# RCS_Cntrl_Board.net
KiCad netlist of a schematic drawn in EAGLE
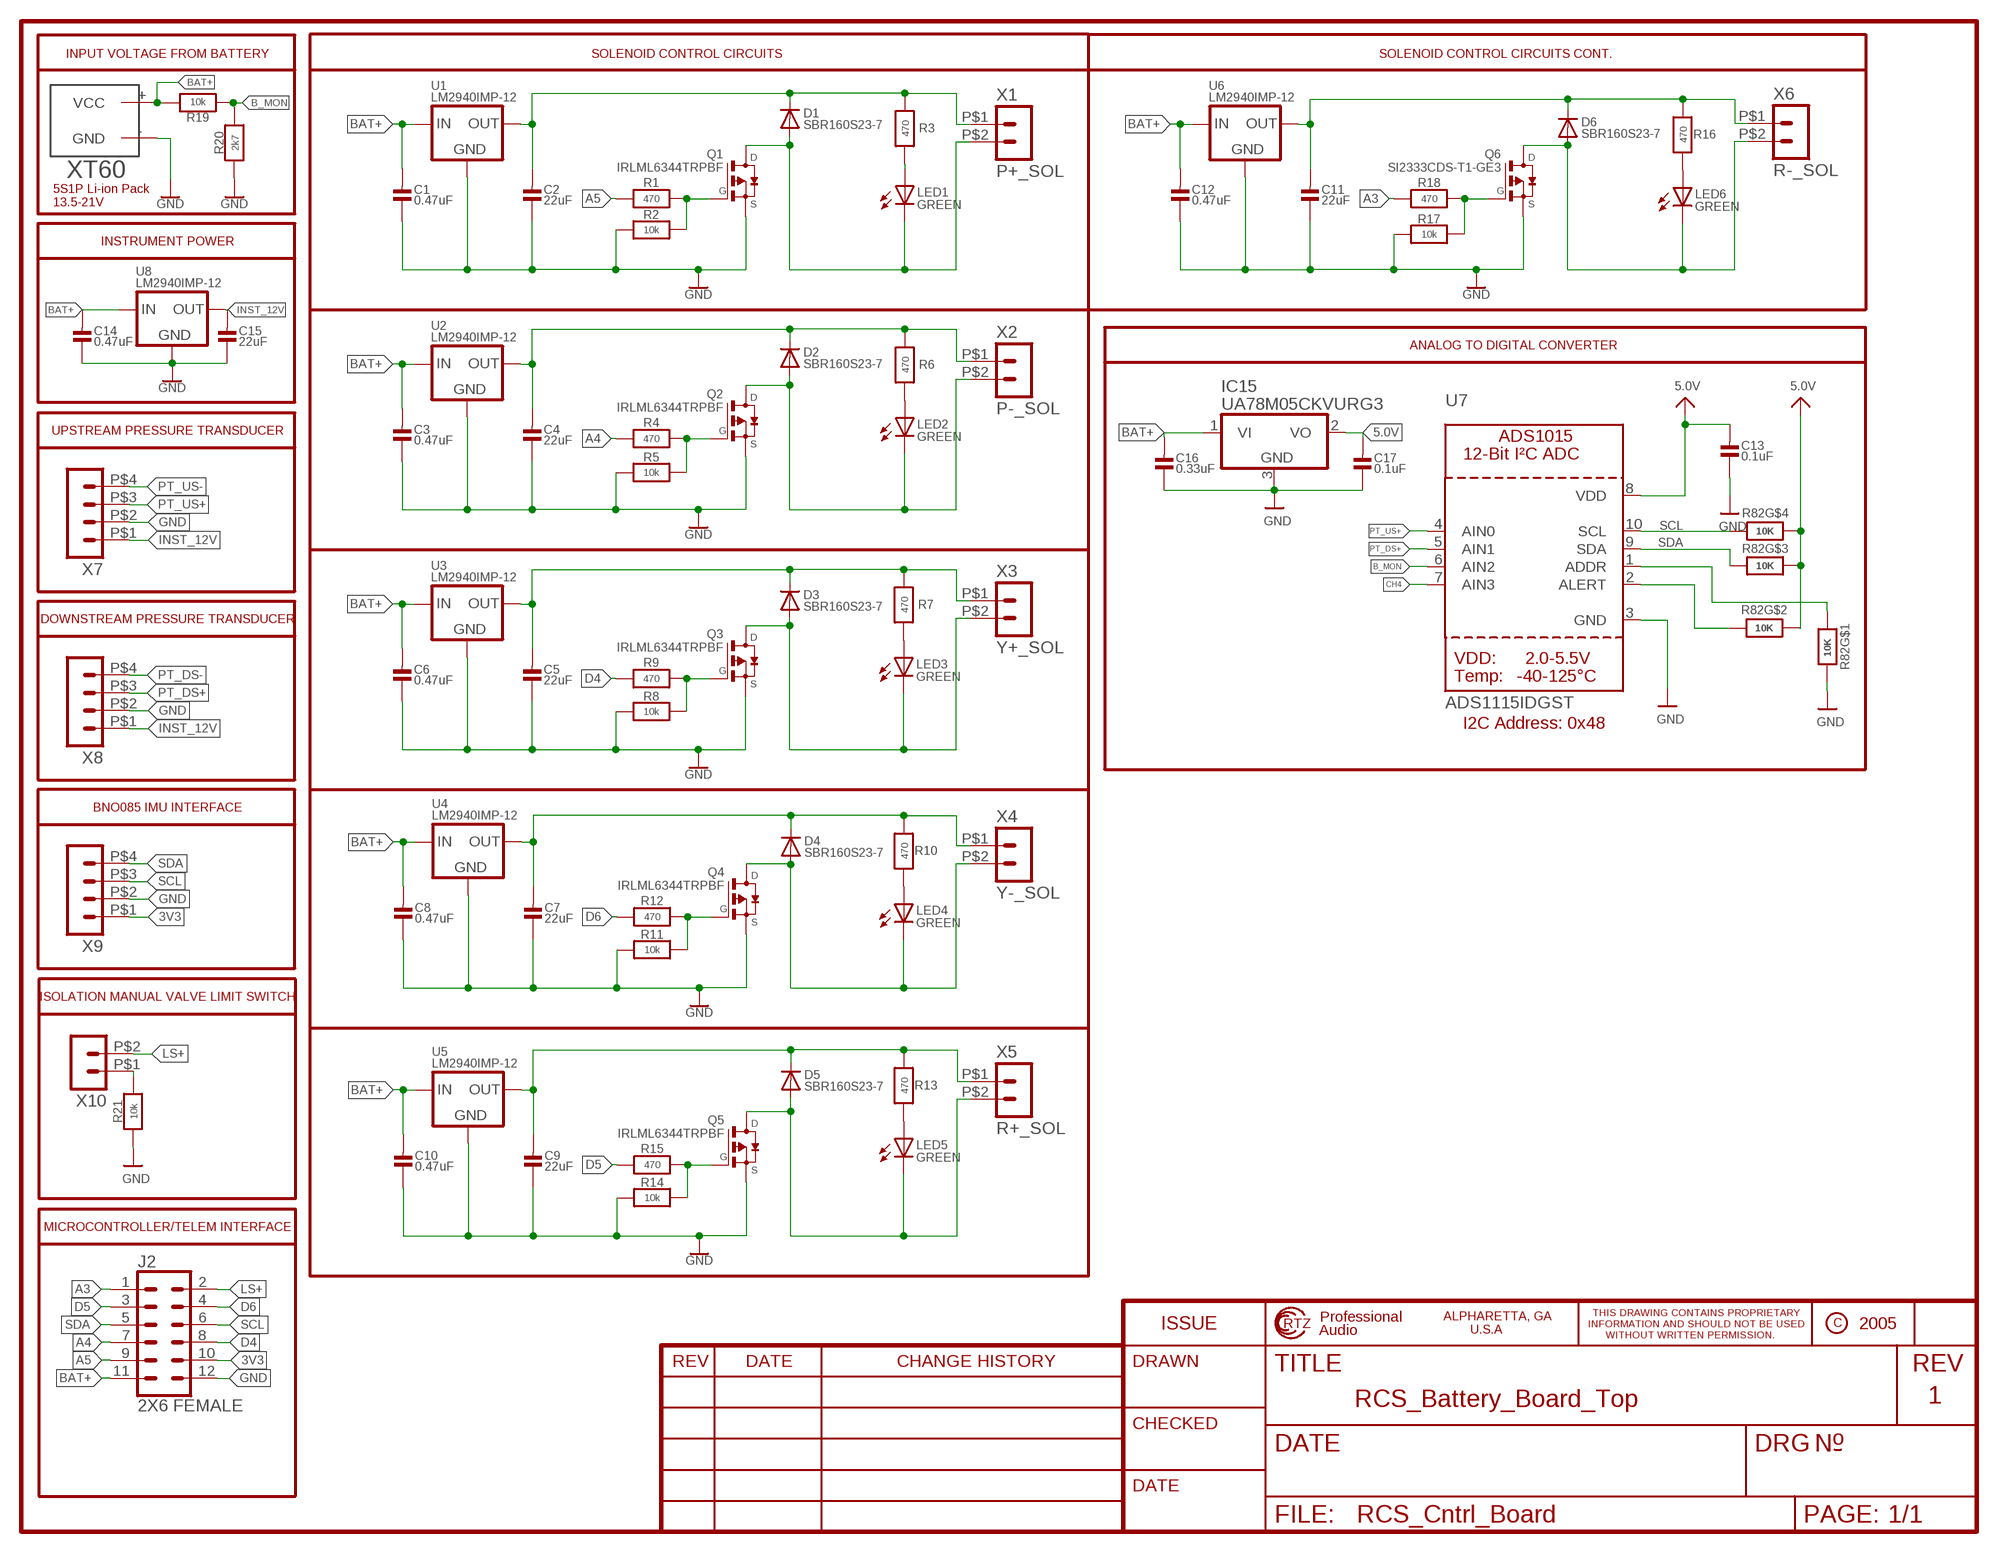
[diagram p0: schematic, sheet 1]

(export (version "E")
  (design (tool "Eeschema 10.0.6"))
  (components
    (comp (ref "C1")
      (value "0.47uF")
      (footprint "eagle-import:0603")
      (libsource (lib "eagle-import") (part "CAP_CERAMIC0603"))
    )
    (comp (ref "C2")
      (value "22uF")
      (footprint "eagle-import:0603")
      (libsource (lib "eagle-import") (part "CAP_CERAMIC0603"))
    )
    (comp (ref "C3")
      (value "0.47uF")
      (footprint "eagle-import:0603")
      (libsource (lib "eagle-import") (part "CAP_CERAMIC0603"))
    )
    (comp (ref "C4")
      (value "22uF")
      (footprint "eagle-import:0603")
      (libsource (lib "eagle-import") (part "CAP_CERAMIC0603"))
    )
    (comp (ref "C5")
      (value "22uF")
      (footprint "eagle-import:0603")
      (libsource (lib "eagle-import") (part "CAP_CERAMIC0603"))
    )
    (comp (ref "C6")
      (value "0.47uF")
      (footprint "eagle-import:0603")
      (libsource (lib "eagle-import") (part "CAP_CERAMIC0603"))
    )
    (comp (ref "C7")
      (value "22uF")
      (footprint "eagle-import:0603")
      (libsource (lib "eagle-import") (part "CAP_CERAMIC0603"))
    )
    (comp (ref "C8")
      (value "0.47uF")
      (footprint "eagle-import:0603")
      (libsource (lib "eagle-import") (part "CAP_CERAMIC0603"))
    )
    (comp (ref "C9")
      (value "22uF")
      (footprint "eagle-import:0603")
      (libsource (lib "eagle-import") (part "CAP_CERAMIC0603"))
    )
    (comp (ref "C10")
      (value "0.47uF")
      (footprint "eagle-import:0603")
      (libsource (lib "eagle-import") (part "CAP_CERAMIC0603"))
    )
    (comp (ref "C11")
      (value "22uF")
      (footprint "eagle-import:0603")
      (libsource (lib "eagle-import") (part "CAP_CERAMIC0603"))
    )
    (comp (ref "C12")
      (value "0.47uF")
      (footprint "eagle-import:0603")
      (libsource (lib "eagle-import") (part "CAP_CERAMIC0603"))
    )
    (comp (ref "C13")
      (value "0.1uF")
      (footprint "eagle-import:0603")
      (libsource (lib "eagle-import") (part "CAP_CERAMIC0603"))
    )
    (comp (ref "C14")
      (value "0.47uF")
      (footprint "eagle-import:0603")
      (libsource (lib "eagle-import") (part "CAP_CERAMIC0603"))
    )
    (comp (ref "C15")
      (value "22uF")
      (footprint "eagle-import:0603")
      (libsource (lib "eagle-import") (part "CAP_CERAMIC0603"))
    )
    (comp (ref "C16")
      (value "0.33uF")
      (footprint "eagle-import:0603")
      (libsource (lib "eagle-import") (part "CAP_CERAMIC0603"))
    )
    (comp (ref "C17")
      (value "0.1uF")
      (footprint "eagle-import:0603")
      (libsource (lib "eagle-import") (part "CAP_CERAMIC0603"))
    )
    (comp (ref "D1")
      (value "SBR160S23-7")
      (footprint "eagle-import:SOT23-R")
      (libsource (lib "eagle-import") (part "DIODESOT23_REFLOW"))
    )
    (comp (ref "D2")
      (value "SBR160S23-7")
      (footprint "eagle-import:SOT23-R")
      (libsource (lib "eagle-import") (part "DIODESOT23_REFLOW"))
    )
    (comp (ref "D3")
      (value "SBR160S23-7")
      (footprint "eagle-import:SOT23-R")
      (libsource (lib "eagle-import") (part "DIODESOT23_REFLOW"))
    )
    (comp (ref "D4")
      (value "SBR160S23-7")
      (footprint "eagle-import:SOT23-R")
      (libsource (lib "eagle-import") (part "DIODESOT23_REFLOW"))
    )
    (comp (ref "D5")
      (value "SBR160S23-7")
      (footprint "eagle-import:SOT23-R")
      (libsource (lib "eagle-import") (part "DIODESOT23_REFLOW"))
    )
    (comp (ref "D6")
      (value "SBR160S23-7")
      (footprint "eagle-import:SOT23-R")
      (libsource (lib "eagle-import") (part "DIODESOT23_REFLOW"))
    )
    (comp (ref "IC15")
      (value "UA78M05CKVURG3")
      (footprint "eagle-import:TO252")
      (libsource (lib "eagle-import") (part "78DT06"))
    )
    (comp (ref "J2")
      (value "2X6 FEMALE")
      (footprint "eagle-import:2X6")
      (libsource (lib "eagle-import") (part "CONN_06X2PTH_FEMALE"))
    )
    (comp (ref "LED1")
      (value "GREEN")
      (footprint "eagle-import:CHIPLED_0603")
      (libsource (lib "eagle-import") (part "LEDCHIPLED_0603"))
    )
    (comp (ref "LED2")
      (value "GREEN")
      (footprint "eagle-import:CHIPLED_0603")
      (libsource (lib "eagle-import") (part "LEDCHIPLED_0603"))
    )
    (comp (ref "LED3")
      (value "GREEN")
      (footprint "eagle-import:CHIPLED_0603")
      (libsource (lib "eagle-import") (part "LEDCHIPLED_0603"))
    )
    (comp (ref "LED4")
      (value "GREEN")
      (footprint "eagle-import:CHIPLED_0603")
      (libsource (lib "eagle-import") (part "LEDCHIPLED_0603"))
    )
    (comp (ref "LED5")
      (value "GREEN")
      (footprint "eagle-import:CHIPLED_0603")
      (libsource (lib "eagle-import") (part "LEDCHIPLED_0603"))
    )
    (comp (ref "LED6")
      (value "GREEN")
      (footprint "eagle-import:CHIPLED_0603")
      (libsource (lib "eagle-import") (part "LEDCHIPLED_0603"))
    )
    (comp (ref "Q1")
      (value "IRLML6344TRPBF")
      (footprint "eagle-import:TRANSISTOR-FET_SOT23")
      (libsource (lib "eagle-import") (part "TRANSISTOR-FET_DMP2004K"))
    )
    (comp (ref "Q2")
      (value "IRLML6344TRPBF")
      (footprint "eagle-import:TRANSISTOR-FET_SOT23")
      (libsource (lib "eagle-import") (part "TRANSISTOR-FET_DMP2004K"))
    )
    (comp (ref "Q3")
      (value "IRLML6344TRPBF")
      (footprint "eagle-import:TRANSISTOR-FET_SOT23")
      (libsource (lib "eagle-import") (part "TRANSISTOR-FET_DMP2004K"))
    )
    (comp (ref "Q4")
      (value "IRLML6344TRPBF")
      (footprint "eagle-import:TRANSISTOR-FET_SOT23")
      (libsource (lib "eagle-import") (part "TRANSISTOR-FET_DMP2004K"))
    )
    (comp (ref "Q5")
      (value "IRLML6344TRPBF")
      (footprint "eagle-import:TRANSISTOR-FET_SOT23")
      (libsource (lib "eagle-import") (part "TRANSISTOR-FET_DMP2004K"))
    )
    (comp (ref "Q6")
      (value "SI2333CDS-T1-GE3")
      (footprint "eagle-import:TRANSISTOR-FET_SOT23")
      (libsource (lib "eagle-import") (part "TRANSISTOR-FET_DMP2004K"))
    )
    (comp (ref "R1")
      (value "470")
      (footprint "eagle-import:0603-NO")
      (libsource (lib "eagle-import") (part "RESISTOR_0603_NOOUT"))
    )
    (comp (ref "R2")
      (value "10k")
      (footprint "eagle-import:0603-NO")
      (libsource (lib "eagle-import") (part "RESISTOR_0603_NOOUT"))
    )
    (comp (ref "R3")
      (value "470")
      (footprint "eagle-import:0603-NO")
      (libsource (lib "eagle-import") (part "RESISTOR_0603_NOOUT"))
    )
    (comp (ref "R4")
      (value "470")
      (footprint "eagle-import:0603-NO")
      (libsource (lib "eagle-import") (part "RESISTOR_0603_NOOUT"))
    )
    (comp (ref "R5")
      (value "10k")
      (footprint "eagle-import:0603-NO")
      (libsource (lib "eagle-import") (part "RESISTOR_0603_NOOUT"))
    )
    (comp (ref "R6")
      (value "470")
      (footprint "eagle-import:0603-NO")
      (libsource (lib "eagle-import") (part "RESISTOR_0603_NOOUT"))
    )
    (comp (ref "R7")
      (value "470")
      (footprint "eagle-import:0603-NO")
      (libsource (lib "eagle-import") (part "RESISTOR_0603_NOOUT"))
    )
    (comp (ref "R8")
      (value "10k")
      (footprint "eagle-import:0603-NO")
      (libsource (lib "eagle-import") (part "RESISTOR_0603_NOOUT"))
    )
    (comp (ref "R9")
      (value "470")
      (footprint "eagle-import:0603-NO")
      (libsource (lib "eagle-import") (part "RESISTOR_0603_NOOUT"))
    )
    (comp (ref "R10")
      (value "470")
      (footprint "eagle-import:0603-NO")
      (libsource (lib "eagle-import") (part "RESISTOR_0603_NOOUT"))
    )
    (comp (ref "R11")
      (value "10k")
      (footprint "eagle-import:0603-NO")
      (libsource (lib "eagle-import") (part "RESISTOR_0603_NOOUT"))
    )
    (comp (ref "R12")
      (value "470")
      (footprint "eagle-import:0603-NO")
      (libsource (lib "eagle-import") (part "RESISTOR_0603_NOOUT"))
    )
    (comp (ref "R13")
      (value "470")
      (footprint "eagle-import:0603-NO")
      (libsource (lib "eagle-import") (part "RESISTOR_0603_NOOUT"))
    )
    (comp (ref "R14")
      (value "10k")
      (footprint "eagle-import:0603-NO")
      (libsource (lib "eagle-import") (part "RESISTOR_0603_NOOUT"))
    )
    (comp (ref "R15")
      (value "470")
      (footprint "eagle-import:0603-NO")
      (libsource (lib "eagle-import") (part "RESISTOR_0603_NOOUT"))
    )
    (comp (ref "R16")
      (value "470")
      (footprint "eagle-import:0603-NO")
      (libsource (lib "eagle-import") (part "RESISTOR_0603_NOOUT"))
    )
    (comp (ref "R17")
      (value "10k")
      (footprint "eagle-import:0603-NO")
      (libsource (lib "eagle-import") (part "RESISTOR_0603_NOOUT"))
    )
    (comp (ref "R18")
      (value "470")
      (footprint "eagle-import:0603-NO")
      (libsource (lib "eagle-import") (part "RESISTOR_0603_NOOUT"))
    )
    (comp (ref "R19")
      (value "10k")
      (footprint "eagle-import:0603-NO")
      (libsource (lib "eagle-import") (part "RESISTOR_0603_NOOUT"))
    )
    (comp (ref "R20")
      (value "2k7")
      (footprint "eagle-import:0603-NO")
      (libsource (lib "eagle-import") (part "RESISTOR_0603_NOOUT"))
    )
    (comp (ref "R21")
      (value "10k")
      (footprint "eagle-import:0603-NO")
      (libsource (lib "eagle-import") (part "RESISTOR_0603_NOOUT"))
    )
    (comp (ref "R82")
      (value "10K")
      (footprint "eagle-import:RESPACK_4X0603")
      (libsource (lib "eagle-import") (part "RESISTOR_4PACK"))
    )
    (comp (ref "U$4")
      (value "XT60")
      (footprint "eagle-import:XT60")
      (libsource (lib "eagle-import") (part "XT60"))
    )
    (comp (ref "U1")
      (value "LM2940IMP-12")
      (footprint "eagle-import:SOT223-R")
      (libsource (lib "eagle-import") (part "LM2940IMP-12/NOPB"))
    )
    (comp (ref "U2")
      (value "LM2940IMP-12")
      (footprint "eagle-import:SOT223-R")
      (libsource (lib "eagle-import") (part "LM2940IMP-12/NOPB"))
    )
    (comp (ref "U3")
      (value "LM2940IMP-12")
      (footprint "eagle-import:SOT223-R")
      (libsource (lib "eagle-import") (part "LM2940IMP-12/NOPB"))
    )
    (comp (ref "U4")
      (value "LM2940IMP-12")
      (footprint "eagle-import:SOT223-R")
      (libsource (lib "eagle-import") (part "LM2940IMP-12/NOPB"))
    )
    (comp (ref "U5")
      (value "LM2940IMP-12")
      (footprint "eagle-import:SOT223-R")
      (libsource (lib "eagle-import") (part "LM2940IMP-12/NOPB"))
    )
    (comp (ref "U6")
      (value "LM2940IMP-12")
      (footprint "eagle-import:SOT223-R")
      (libsource (lib "eagle-import") (part "LM2940IMP-12/NOPB"))
    )
    (comp (ref "U7")
      (value "ADS1115IDGST")
      (footprint "eagle-import:MSOP10")
      (libsource (lib "eagle-import") (part "ADC_ADS1015"))
    )
    (comp (ref "U8")
      (value "LM2940IMP-12")
      (footprint "eagle-import:SOT223-R")
      (libsource (lib "eagle-import") (part "LM2940IMP-12/NOPB"))
    )
    (comp (ref "X1")
      (value "P+_SOL")
      (footprint "eagle-import:44914-0201")
      (libsource (lib "eagle-import") (part "HEADER_POS2_?44914-0201"))
    )
    (comp (ref "X2")
      (value "P-_SOL")
      (footprint "eagle-import:44914-0201")
      (libsource (lib "eagle-import") (part "HEADER_POS2_?44914-0201"))
    )
    (comp (ref "X3")
      (value "Y+_SOL")
      (footprint "eagle-import:44914-0201")
      (libsource (lib "eagle-import") (part "HEADER_POS2_?44914-0201"))
    )
    (comp (ref "X4")
      (value "Y-_SOL")
      (footprint "eagle-import:44914-0201")
      (libsource (lib "eagle-import") (part "HEADER_POS2_?44914-0201"))
    )
    (comp (ref "X5")
      (value "R+_SOL")
      (footprint "eagle-import:44914-0201")
      (libsource (lib "eagle-import") (part "HEADER_POS2_?44914-0201"))
    )
    (comp (ref "X6")
      (value "R-_SOL")
      (footprint "eagle-import:44914-0201")
      (libsource (lib "eagle-import") (part "HEADER_POS2_?44914-0201"))
    )
    (comp (ref "X7")
      (value "HEADER_POS4_43650-0415")
      (footprint "eagle-import:43650-0415")
      (libsource (lib "eagle-import") (part "HEADER_POS4_?43650-0415"))
    )
    (comp (ref "X8")
      (value "HEADER_POS4_43650-0415")
      (footprint "eagle-import:43650-0415")
      (libsource (lib "eagle-import") (part "HEADER_POS4_?43650-0415"))
    )
    (comp (ref "X9")
      (value "HEADER_POS4_43650-0415")
      (footprint "eagle-import:43650-0415")
      (libsource (lib "eagle-import") (part "HEADER_POS4_?43650-0415"))
    )
    (comp (ref "X10")
      (value "HEADER_POS2_43650-0215")
      (footprint "eagle-import:43650-0215")
      (libsource (lib "eagle-import") (part "HEADER_POS2_?43650-0215"))
    )
  )
  (nets
    (net (code "1") (name "3V3") (class "Default")
      (node (ref "J2") (pin "10") (pinfunction "10_10") (pintype "passive"))
      (node (ref "X9") (pin "P$1") (pinfunction "1_P$1") (pintype "passive"))
    )
    (net (code "2") (name "5.0V") (class "Default")
      (node (ref "C13") (pin "2") (pinfunction "P$2_2") (pintype "passive"))
      (node (ref "C17") (pin "2") (pinfunction "P$2_2") (pintype "passive"))
      (node (ref "IC15") (pin "2") (pinfunction "VO_2") (pintype "passive"))
      (node (ref "R82") (pin "5") (pinfunction "2_5") (pintype "passive"))
      (node (ref "R82") (pin "6") (pinfunction "2_6") (pintype "passive"))
      (node (ref "R82") (pin "7") (pinfunction "2_7") (pintype "passive"))
      (node (ref "U7") (pin "8") (pinfunction "VDD_8") (pintype "bidirectional"))
    )
    (net (code "3") (name "A3") (class "Default")
      (node (ref "J2") (pin "1") (pinfunction "1_1") (pintype "passive"))
      (node (ref "R18") (pin "1") (pinfunction "1_1") (pintype "passive"))
    )
    (net (code "4") (name "A4") (class "Default")
      (node (ref "J2") (pin "7") (pinfunction "7_7") (pintype "passive"))
      (node (ref "R4") (pin "1") (pinfunction "1_1") (pintype "passive"))
    )
    (net (code "5") (name "A5") (class "Default")
      (node (ref "J2") (pin "9") (pinfunction "9_9") (pintype "passive"))
      (node (ref "R1") (pin "1") (pinfunction "1_1") (pintype "passive"))
    )
    (net (code "6") (name "BAT+") (class "Default")
      (node (ref "C1") (pin "2") (pinfunction "P$2_2") (pintype "passive"))
      (node (ref "C10") (pin "2") (pinfunction "P$2_2") (pintype "passive"))
      (node (ref "C12") (pin "2") (pinfunction "P$2_2") (pintype "passive"))
      (node (ref "C14") (pin "2") (pinfunction "P$2_2") (pintype "passive"))
      (node (ref "C16") (pin "2") (pinfunction "P$2_2") (pintype "passive"))
      (node (ref "C3") (pin "2") (pinfunction "P$2_2") (pintype "passive"))
      (node (ref "C6") (pin "2") (pinfunction "P$2_2") (pintype "passive"))
      (node (ref "C8") (pin "2") (pinfunction "P$2_2") (pintype "passive"))
      (node (ref "IC15") (pin "1") (pinfunction "VI_1") (pintype "input"))
      (node (ref "J2") (pin "11") (pinfunction "11_11") (pintype "passive"))
      (node (ref "R19") (pin "2") (pinfunction "2_2") (pintype "passive"))
      (node (ref "U$4") (pin "+") (pinfunction "VCC_+") (pintype "bidirectional"))
      (node (ref "U1") (pin "1") (pinfunction "IN_1") (pintype "input"))
      (node (ref "U2") (pin "1") (pinfunction "IN_1") (pintype "input"))
      (node (ref "U3") (pin "1") (pinfunction "IN_1") (pintype "input"))
      (node (ref "U4") (pin "1") (pinfunction "IN_1") (pintype "input"))
      (node (ref "U5") (pin "1") (pinfunction "IN_1") (pintype "input"))
      (node (ref "U6") (pin "1") (pinfunction "IN_1") (pintype "input"))
      (node (ref "U8") (pin "1") (pinfunction "IN_1") (pintype "input"))
    )
    (net (code "7") (name "B_MON") (class "Default")
      (node (ref "R19") (pin "1") (pinfunction "1_1") (pintype "passive"))
      (node (ref "R20") (pin "2") (pinfunction "2_2") (pintype "passive"))
      (node (ref "U7") (pin "6") (pinfunction "AIN2_6") (pintype "bidirectional"))
    )
    (net (code "8") (name "CH4") (class "Default")
      (node (ref "U7") (pin "7") (pinfunction "AIN3_7") (pintype "bidirectional"))
    )
    (net (code "9") (name "D4") (class "Default")
      (node (ref "J2") (pin "8") (pinfunction "8_8") (pintype "passive"))
      (node (ref "R9") (pin "1") (pinfunction "1_1") (pintype "passive"))
    )
    (net (code "10") (name "D5") (class "Default")
      (node (ref "J2") (pin "3") (pinfunction "3_3") (pintype "passive"))
      (node (ref "R15") (pin "1") (pinfunction "1_1") (pintype "passive"))
    )
    (net (code "11") (name "D6") (class "Default")
      (node (ref "J2") (pin "4") (pinfunction "4_4") (pintype "passive"))
      (node (ref "R12") (pin "1") (pinfunction "1_1") (pintype "passive"))
    )
    (net (code "12") (name "GND") (class "Default")
      (node (ref "C1") (pin "1") (pinfunction "P$1_1") (pintype "passive"))
      (node (ref "C10") (pin "1") (pinfunction "P$1_1") (pintype "passive"))
      (node (ref "C11") (pin "1") (pinfunction "P$1_1") (pintype "passive"))
      (node (ref "C12") (pin "1") (pinfunction "P$1_1") (pintype "passive"))
      (node (ref "C13") (pin "1") (pinfunction "P$1_1") (pintype "passive"))
      (node (ref "C14") (pin "1") (pinfunction "P$1_1") (pintype "passive"))
      (node (ref "C15") (pin "1") (pinfunction "P$1_1") (pintype "passive"))
      (node (ref "C16") (pin "1") (pinfunction "P$1_1") (pintype "passive"))
      (node (ref "C17") (pin "1") (pinfunction "P$1_1") (pintype "passive"))
      (node (ref "C2") (pin "1") (pinfunction "P$1_1") (pintype "passive"))
      (node (ref "C3") (pin "1") (pinfunction "P$1_1") (pintype "passive"))
      (node (ref "C4") (pin "1") (pinfunction "P$1_1") (pintype "passive"))
      (node (ref "C5") (pin "1") (pinfunction "P$1_1") (pintype "passive"))
      (node (ref "C6") (pin "1") (pinfunction "P$1_1") (pintype "passive"))
      (node (ref "C7") (pin "1") (pinfunction "P$1_1") (pintype "passive"))
      (node (ref "C8") (pin "1") (pinfunction "P$1_1") (pintype "passive"))
      (node (ref "C9") (pin "1") (pinfunction "P$1_1") (pintype "passive"))
      (node (ref "IC15") (pin "3") (pinfunction "GND_3") (pintype "passive"))
      (node (ref "J2") (pin "12") (pinfunction "12_12") (pintype "passive"))
      (node (ref "Q1") (pin "2") (pinfunction "S_2") (pintype "passive"))
      (node (ref "Q2") (pin "2") (pinfunction "S_2") (pintype "passive"))
      (node (ref "Q3") (pin "2") (pinfunction "S_2") (pintype "passive"))
      (node (ref "Q4") (pin "2") (pinfunction "S_2") (pintype "passive"))
      (node (ref "Q5") (pin "2") (pinfunction "S_2") (pintype "passive"))
      (node (ref "Q6") (pin "2") (pinfunction "S_2") (pintype "passive"))
      (node (ref "R11") (pin "1") (pinfunction "1_1") (pintype "passive"))
      (node (ref "R14") (pin "1") (pinfunction "1_1") (pintype "passive"))
      (node (ref "R17") (pin "1") (pinfunction "1_1") (pintype "passive"))
      (node (ref "R2") (pin "1") (pinfunction "1_1") (pintype "passive"))
      (node (ref "R20") (pin "1") (pinfunction "1_1") (pintype "passive"))
      (node (ref "R21") (pin "1") (pinfunction "1_1") (pintype "passive"))
      (node (ref "R5") (pin "1") (pinfunction "1_1") (pintype "passive"))
      (node (ref "R8") (pin "1") (pinfunction "1_1") (pintype "passive"))
      (node (ref "R82") (pin "8") (pinfunction "2_8") (pintype "passive"))
      (node (ref "U$4") (pin "-") (pinfunction "GND_-") (pintype "bidirectional"))
      (node (ref "U1") (pin "2") (pinfunction "GND_2") (pintype "input"))
      (node (ref "U2") (pin "2") (pinfunction "GND_2") (pintype "input"))
      (node (ref "U3") (pin "2") (pinfunction "GND_2") (pintype "input"))
      (node (ref "U4") (pin "2") (pinfunction "GND_2") (pintype "input"))
      (node (ref "U5") (pin "2") (pinfunction "GND_2") (pintype "input"))
      (node (ref "U6") (pin "2") (pinfunction "GND_2") (pintype "input"))
      (node (ref "U7") (pin "3") (pinfunction "GND_3") (pintype "bidirectional"))
      (node (ref "U8") (pin "2") (pinfunction "GND_2") (pintype "input"))
      (node (ref "X7") (pin "P$2") (pinfunction "2_P$2") (pintype "passive"))
      (node (ref "X8") (pin "P$2") (pinfunction "2_P$2") (pintype "passive"))
      (node (ref "X9") (pin "P$2") (pinfunction "2_P$2") (pintype "passive"))
    )
    (net (code "13") (name "INST_12V") (class "Default")
      (node (ref "C15") (pin "2") (pinfunction "P$2_2") (pintype "passive"))
      (node (ref "U8") (pin "3") (pinfunction "OUT_3") (pintype "passive"))
      (node (ref "X7") (pin "P$1") (pinfunction "1_P$1") (pintype "passive"))
      (node (ref "X8") (pin "P$1") (pinfunction "1_P$1") (pintype "passive"))
    )
    (net (code "14") (name "LS+") (class "Default")
      (node (ref "J2") (pin "2") (pinfunction "2_2") (pintype "passive"))
      (node (ref "X10") (pin "P$2") (pinfunction "2_P$2") (pintype "passive"))
    )
    (net (code "15") (name "Net-(C2-P$2)") (class "Default")
      (node (ref "C2") (pin "2") (pinfunction "P$2_2") (pintype "passive"))
      (node (ref "D1") (pin "3") (pinfunction "C_3") (pintype "passive"))
      (node (ref "R3") (pin "2") (pinfunction "2_2") (pintype "passive"))
      (node (ref "U1") (pin "3") (pinfunction "OUT_3") (pintype "passive"))
      (node (ref "X1") (pin "P$1") (pinfunction "1_P$1") (pintype "passive"))
    )
    (net (code "16") (name "Net-(C4-P$2)") (class "Default")
      (node (ref "C4") (pin "2") (pinfunction "P$2_2") (pintype "passive"))
      (node (ref "D2") (pin "3") (pinfunction "C_3") (pintype "passive"))
      (node (ref "R6") (pin "2") (pinfunction "2_2") (pintype "passive"))
      (node (ref "U2") (pin "3") (pinfunction "OUT_3") (pintype "passive"))
      (node (ref "X2") (pin "P$1") (pinfunction "1_P$1") (pintype "passive"))
    )
    (net (code "17") (name "Net-(C5-P$2)") (class "Default")
      (node (ref "C5") (pin "2") (pinfunction "P$2_2") (pintype "passive"))
      (node (ref "D3") (pin "3") (pinfunction "C_3") (pintype "passive"))
      (node (ref "R7") (pin "2") (pinfunction "2_2") (pintype "passive"))
      (node (ref "U3") (pin "3") (pinfunction "OUT_3") (pintype "passive"))
      (node (ref "X3") (pin "P$1") (pinfunction "1_P$1") (pintype "passive"))
    )
    (net (code "18") (name "Net-(C7-P$2)") (class "Default")
      (node (ref "C7") (pin "2") (pinfunction "P$2_2") (pintype "passive"))
      (node (ref "D4") (pin "3") (pinfunction "C_3") (pintype "passive"))
      (node (ref "R10") (pin "2") (pinfunction "2_2") (pintype "passive"))
      (node (ref "U4") (pin "3") (pinfunction "OUT_3") (pintype "passive"))
      (node (ref "X4") (pin "P$1") (pinfunction "1_P$1") (pintype "passive"))
    )
    (net (code "19") (name "Net-(C9-P$2)") (class "Default")
      (node (ref "C9") (pin "2") (pinfunction "P$2_2") (pintype "passive"))
      (node (ref "D5") (pin "3") (pinfunction "C_3") (pintype "passive"))
      (node (ref "R13") (pin "2") (pinfunction "2_2") (pintype "passive"))
      (node (ref "U5") (pin "3") (pinfunction "OUT_3") (pintype "passive"))
      (node (ref "X5") (pin "P$1") (pinfunction "1_P$1") (pintype "passive"))
    )
    (net (code "20") (name "Net-(C11-P$2)") (class "Default")
      (node (ref "C11") (pin "2") (pinfunction "P$2_2") (pintype "passive"))
      (node (ref "D6") (pin "3") (pinfunction "C_3") (pintype "passive"))
      (node (ref "R16") (pin "2") (pinfunction "2_2") (pintype "passive"))
      (node (ref "U6") (pin "3") (pinfunction "OUT_3") (pintype "passive"))
      (node (ref "X6") (pin "P$1") (pinfunction "1_P$1") (pintype "passive"))
    )
    (net (code "21") (name "Net-(D1-A)") (class "Default")
      (node (ref "D1") (pin "1") (pinfunction "A_1") (pintype "passive"))
      (node (ref "LED1") (pin "C") (pinfunction "C_C") (pintype "passive"))
      (node (ref "Q1") (pin "3") (pinfunction "D_3") (pintype "passive"))
      (node (ref "X1") (pin "P$2") (pinfunction "2_P$2") (pintype "passive"))
    )
    (net (code "22") (name "Net-(D2-A)") (class "Default")
      (node (ref "D2") (pin "1") (pinfunction "A_1") (pintype "passive"))
      (node (ref "LED2") (pin "C") (pinfunction "C_C") (pintype "passive"))
      (node (ref "Q2") (pin "3") (pinfunction "D_3") (pintype "passive"))
      (node (ref "X2") (pin "P$2") (pinfunction "2_P$2") (pintype "passive"))
    )
    (net (code "23") (name "Net-(D3-A)") (class "Default")
      (node (ref "D3") (pin "1") (pinfunction "A_1") (pintype "passive"))
      (node (ref "LED3") (pin "C") (pinfunction "C_C") (pintype "passive"))
      (node (ref "Q3") (pin "3") (pinfunction "D_3") (pintype "passive"))
      (node (ref "X3") (pin "P$2") (pinfunction "2_P$2") (pintype "passive"))
    )
    (net (code "24") (name "Net-(D4-A)") (class "Default")
      (node (ref "D4") (pin "1") (pinfunction "A_1") (pintype "passive"))
      (node (ref "LED4") (pin "C") (pinfunction "C_C") (pintype "passive"))
      (node (ref "Q4") (pin "3") (pinfunction "D_3") (pintype "passive"))
      (node (ref "X4") (pin "P$2") (pinfunction "2_P$2") (pintype "passive"))
    )
    (net (code "25") (name "Net-(D5-A)") (class "Default")
      (node (ref "D5") (pin "1") (pinfunction "A_1") (pintype "passive"))
      (node (ref "LED5") (pin "C") (pinfunction "C_C") (pintype "passive"))
      (node (ref "Q5") (pin "3") (pinfunction "D_3") (pintype "passive"))
      (node (ref "X5") (pin "P$2") (pinfunction "2_P$2") (pintype "passive"))
    )
    (net (code "26") (name "Net-(D6-A)") (class "Default")
      (node (ref "D6") (pin "1") (pinfunction "A_1") (pintype "passive"))
      (node (ref "LED6") (pin "C") (pinfunction "C_C") (pintype "passive"))
      (node (ref "Q6") (pin "3") (pinfunction "D_3") (pintype "passive"))
      (node (ref "X6") (pin "P$2") (pinfunction "2_P$2") (pintype "passive"))
    )
    (net (code "27") (name "Net-(LED1-PadA)") (class "Default")
      (node (ref "LED1") (pin "A") (pinfunction "A_A") (pintype "passive"))
      (node (ref "R3") (pin "1") (pinfunction "1_1") (pintype "passive"))
    )
    (net (code "28") (name "Net-(LED2-PadA)") (class "Default")
      (node (ref "LED2") (pin "A") (pinfunction "A_A") (pintype "passive"))
      (node (ref "R6") (pin "1") (pinfunction "1_1") (pintype "passive"))
    )
    (net (code "29") (name "Net-(LED3-PadA)") (class "Default")
      (node (ref "LED3") (pin "A") (pinfunction "A_A") (pintype "passive"))
      (node (ref "R7") (pin "1") (pinfunction "1_1") (pintype "passive"))
    )
    (net (code "30") (name "Net-(LED4-PadA)") (class "Default")
      (node (ref "LED4") (pin "A") (pinfunction "A_A") (pintype "passive"))
      (node (ref "R10") (pin "1") (pinfunction "1_1") (pintype "passive"))
    )
    (net (code "31") (name "Net-(LED5-PadA)") (class "Default")
      (node (ref "LED5") (pin "A") (pinfunction "A_A") (pintype "passive"))
      (node (ref "R13") (pin "1") (pinfunction "1_1") (pintype "passive"))
    )
    (net (code "32") (name "Net-(LED6-PadA)") (class "Default")
      (node (ref "LED6") (pin "A") (pinfunction "A_A") (pintype "passive"))
      (node (ref "R16") (pin "1") (pinfunction "1_1") (pintype "passive"))
    )
    (net (code "33") (name "Net-(Q1-G)") (class "Default")
      (node (ref "Q1") (pin "1") (pinfunction "G_1") (pintype "passive"))
      (node (ref "R1") (pin "2") (pinfunction "2_2") (pintype "passive"))
      (node (ref "R2") (pin "2") (pinfunction "2_2") (pintype "passive"))
    )
    (net (code "34") (name "Net-(Q2-G)") (class "Default")
      (node (ref "Q2") (pin "1") (pinfunction "G_1") (pintype "passive"))
      (node (ref "R4") (pin "2") (pinfunction "2_2") (pintype "passive"))
      (node (ref "R5") (pin "2") (pinfunction "2_2") (pintype "passive"))
    )
    (net (code "35") (name "Net-(Q3-G)") (class "Default")
      (node (ref "Q3") (pin "1") (pinfunction "G_1") (pintype "passive"))
      (node (ref "R8") (pin "2") (pinfunction "2_2") (pintype "passive"))
      (node (ref "R9") (pin "2") (pinfunction "2_2") (pintype "passive"))
    )
    (net (code "36") (name "Net-(Q4-G)") (class "Default")
      (node (ref "Q4") (pin "1") (pinfunction "G_1") (pintype "passive"))
      (node (ref "R11") (pin "2") (pinfunction "2_2") (pintype "passive"))
      (node (ref "R12") (pin "2") (pinfunction "2_2") (pintype "passive"))
    )
    (net (code "37") (name "Net-(Q5-G)") (class "Default")
      (node (ref "Q5") (pin "1") (pinfunction "G_1") (pintype "passive"))
      (node (ref "R14") (pin "2") (pinfunction "2_2") (pintype "passive"))
      (node (ref "R15") (pin "2") (pinfunction "2_2") (pintype "passive"))
    )
    (net (code "38") (name "Net-(Q6-G)") (class "Default")
      (node (ref "Q6") (pin "1") (pinfunction "G_1") (pintype "passive"))
      (node (ref "R17") (pin "2") (pinfunction "2_2") (pintype "passive"))
      (node (ref "R18") (pin "2") (pinfunction "2_2") (pintype "passive"))
    )
    (net (code "39") (name "Net-(R82B-1)") (class "Default")
      (node (ref "R82") (pin "2") (pinfunction "1_2") (pintype "passive"))
      (node (ref "U7") (pin "2") (pinfunction "ALERT_2") (pintype "bidirectional"))
    )
    (net (code "40") (name "Net-(U7-ADDR)") (class "Default")
      (node (ref "R82") (pin "1") (pinfunction "1_1") (pintype "passive"))
      (node (ref "U7") (pin "1") (pinfunction "ADDR_1") (pintype "bidirectional"))
    )
    (net (code "41") (name "Net-(X10-1)") (class "Default")
      (node (ref "R21") (pin "2") (pinfunction "2_2") (pintype "passive"))
      (node (ref "X10") (pin "P$1") (pinfunction "1_P$1") (pintype "passive"))
    )
    (net (code "42") (name "PT_DS+") (class "Default")
      (node (ref "U7") (pin "5") (pinfunction "AIN1_5") (pintype "bidirectional"))
      (node (ref "X8") (pin "P$3") (pinfunction "3_P$3") (pintype "passive"))
    )
    (net (code "43") (name "PT_DS-") (class "Default")
      (node (ref "X8") (pin "P$4") (pinfunction "4_P$4") (pintype "passive"))
    )
    (net (code "44") (name "PT_US+") (class "Default")
      (node (ref "U7") (pin "4") (pinfunction "AIN0_4") (pintype "bidirectional"))
      (node (ref "X7") (pin "P$3") (pinfunction "3_P$3") (pintype "passive"))
    )
    (net (code "45") (name "PT_US-") (class "Default")
      (node (ref "X7") (pin "P$4") (pinfunction "4_P$4") (pintype "passive"))
    )
    (net (code "46") (name "SCL") (class "Default")
      (node (ref "J2") (pin "6") (pinfunction "6_6") (pintype "passive"))
      (node (ref "R82") (pin "4") (pinfunction "1_4") (pintype "passive"))
      (node (ref "U7") (pin "10") (pinfunction "SCL_10") (pintype "bidirectional"))
      (node (ref "X9") (pin "P$3") (pinfunction "3_P$3") (pintype "passive"))
    )
    (net (code "47") (name "SDA") (class "Default")
      (node (ref "J2") (pin "5") (pinfunction "5_5") (pintype "passive"))
      (node (ref "R82") (pin "3") (pinfunction "1_3") (pintype "passive"))
      (node (ref "U7") (pin "9") (pinfunction "SDA_9") (pintype "bidirectional"))
      (node (ref "X9") (pin "P$4") (pinfunction "4_P$4") (pintype "passive"))
    )
  )
)
